# CtDSP_IO.net
KiCad netlist of a schematic drawn in Altium Designer
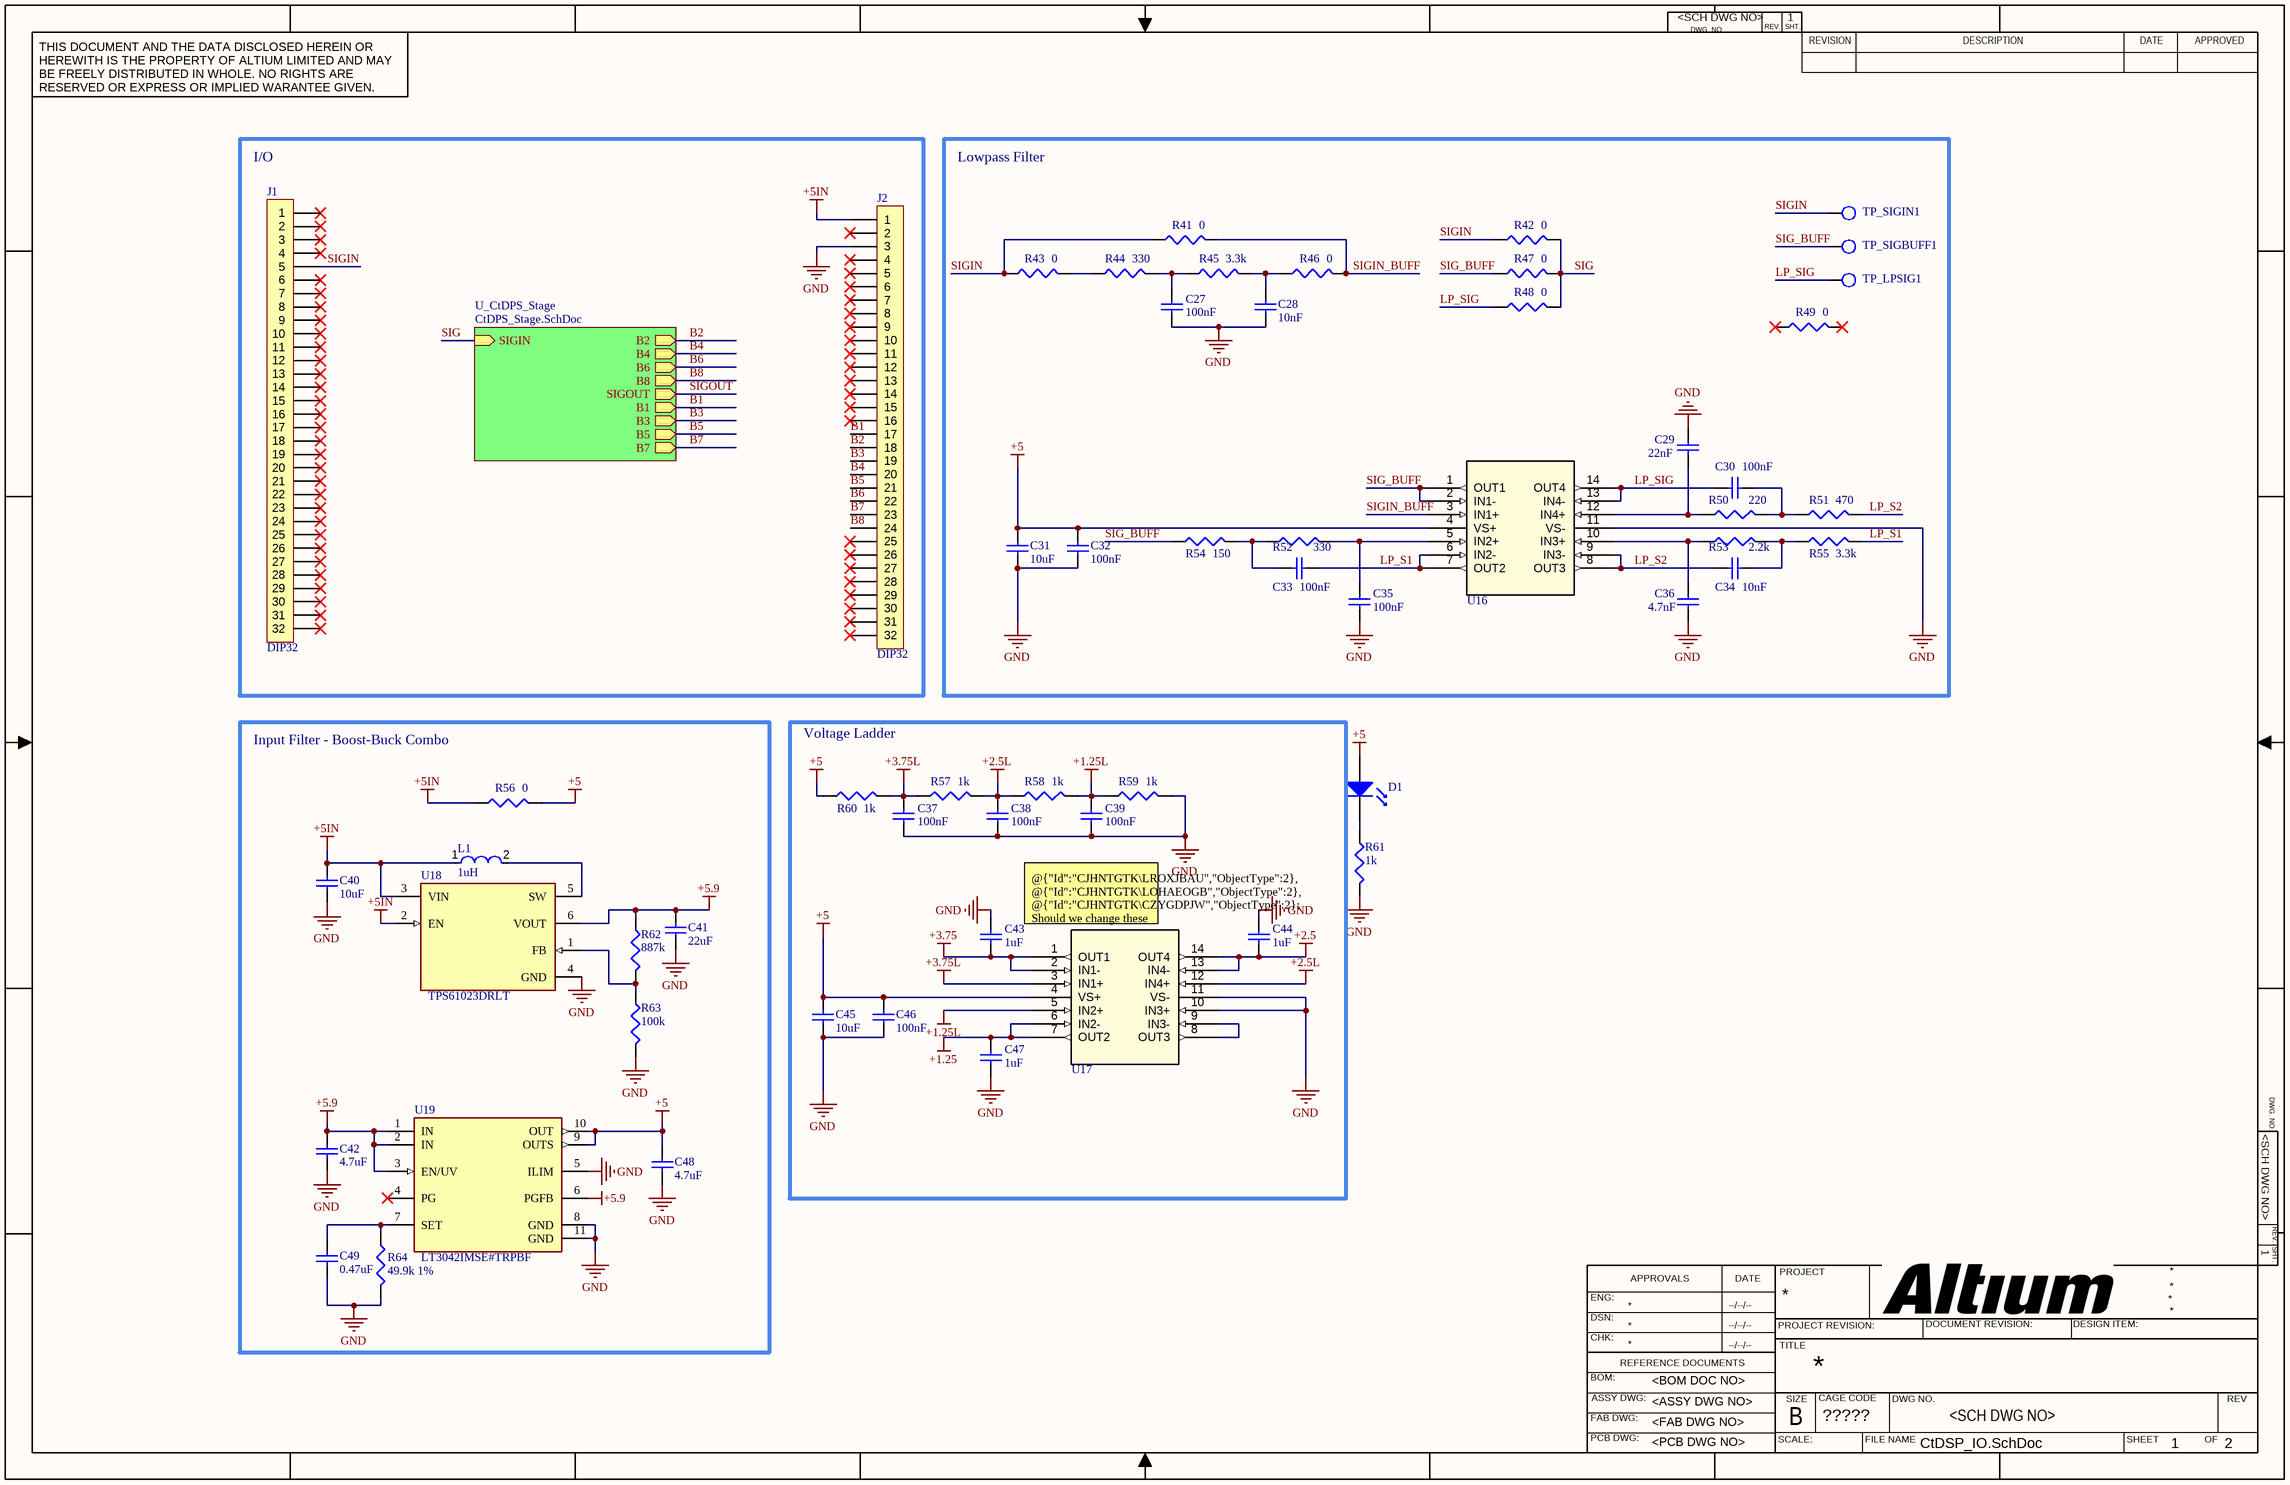
[diagram p0: CtDSP_IO.SchDoc]

(export (version "E")
  (design (tool "Eeschema 10.0.6"))
  (components
    (comp (ref "C27")
      (value "100nF")
      (footprint "C_0402")
      (fields (field (name "LCSC PART #") "C1525"))
      (libsource (lib "ctdsp") (part "C_0402"))
    )
    (comp (ref "C28")
      (value "10nF")
      (footprint "C_0402")
      (fields (field (name "LCSC PART #") "C15195"))
      (libsource (lib "ctdsp") (part "C_0402"))
    )
    (comp (ref "C29")
      (value "22nF")
      (footprint "C_0402")
      (fields (field (name "LCSC PART #") "C1532"))
      (libsource (lib "ctdsp") (part "C_0402"))
    )
    (comp (ref "C30")
      (value "100nF")
      (footprint "C_0402")
      (fields (field (name "LCSC PART #") "C1525"))
      (libsource (lib "ctdsp") (part "C_0402"))
    )
    (comp (ref "C31")
      (value "10uF")
      (footprint "C_0402")
      (fields (field (name "LCSC PART #") "C15525"))
      (libsource (lib "ctdsp") (part "C_0402"))
    )
    (comp (ref "C32")
      (value "100nF")
      (footprint "C_0402")
      (fields (field (name "LCSC PART #") "C1525"))
      (libsource (lib "ctdsp") (part "C_0402"))
    )
    (comp (ref "C33")
      (value "100nF")
      (footprint "C_0402")
      (fields (field (name "LCSC PART #") "C1525"))
      (libsource (lib "ctdsp") (part "C_0402"))
    )
    (comp (ref "C34")
      (value "10nF")
      (footprint "C_0402")
      (fields (field (name "LCSC PART #") "C15195"))
      (libsource (lib "ctdsp") (part "C_0402"))
    )
    (comp (ref "C35")
      (value "100nF")
      (footprint "C_0402")
      (fields (field (name "LCSC PART #") "C1525"))
      (libsource (lib "ctdsp") (part "C_0402"))
    )
    (comp (ref "C36")
      (value "4.7nF")
      (footprint "C_0402")
      (fields (field (name "LCSC PART #") "C1538"))
      (libsource (lib "ctdsp") (part "C_0402"))
    )
    (comp (ref "C37")
      (value "100nF")
      (footprint "C_0402")
      (fields (field (name "LCSC PART #") "C1525"))
      (libsource (lib "ctdsp") (part "C_0402"))
    )
    (comp (ref "C38")
      (value "100nF")
      (footprint "C_0402")
      (fields (field (name "LCSC PART #") "C1525"))
      (libsource (lib "ctdsp") (part "C_0402"))
    )
    (comp (ref "C39")
      (value "100nF")
      (footprint "C_0402")
      (fields (field (name "LCSC PART #") "C1525"))
      (libsource (lib "ctdsp") (part "C_0402"))
    )
    (comp (ref "C40")
      (value "10uF")
      (footprint "C_0402")
      (fields (field (name "LCSC PART #") "C15525"))
      (libsource (lib "ctdsp") (part "C_0402"))
    )
    (comp (ref "C41")
      (value "22uF")
      (footprint "C_0603")
      (fields (field (name "LCSC PART #") "C59461"))
      (libsource (lib "ctdsp") (part "C_0402"))
    )
    (comp (ref "C42")
      (value "4.7uF")
      (footprint "C_0603")
      (fields (field (name "LCSC PART #") "C19666"))
      (libsource (lib "ctdsp") (part "C_0402"))
    )
    (comp (ref "C43")
      (value "1uF")
      (footprint "C_0603")
      (fields (field (name "LCSC PART #") "C15849"))
      (libsource (lib "ctdsp") (part "C_0603"))
    )
    (comp (ref "C44")
      (value "1uF")
      (footprint "C_0603")
      (fields (field (name "LCSC PART #") "C15849"))
      (libsource (lib "ctdsp") (part "C_0603"))
    )
    (comp (ref "C45")
      (value "10uF")
      (footprint "C_0402")
      (fields (field (name "LCSC PART #") "C15525"))
      (libsource (lib "ctdsp") (part "C_0402"))
    )
    (comp (ref "C46")
      (value "100nF")
      (footprint "C_0402")
      (fields (field (name "LCSC PART #") "C1525"))
      (libsource (lib "ctdsp") (part "C_0402"))
    )
    (comp (ref "C47")
      (value "1uF")
      (footprint "C_0603")
      (fields (field (name "LCSC PART #") "C15849"))
      (libsource (lib "ctdsp") (part "C_0603"))
    )
    (comp (ref "C48")
      (value "4.7uF")
      (footprint "C_0603")
      (fields (field (name "LCSC PART #") "C19666"))
      (libsource (lib "ctdsp") (part "C_0402"))
    )
    (comp (ref "C49")
      (value "0.47uF")
      (footprint "C_0603")
      (fields (field (name "LCSC PART #") "C1623"))
      (libsource (lib "ctdsp") (part "C_0402"))
    )
    (comp (ref "D1")
      (value "LED_0603")
      (footprint "LED_6003")
      (fields (field (name "LCSC PART #") "C2286"))
      (libsource (lib "ctdsp") (part "LED_0603"))
    )
    (comp (ref "J1") (value "DIP32") (footprint "DIP32") (libsource (lib "") (part "DIP32_1")))
    (comp (ref "J2") (value "DIP32") (footprint "DIP32") (libsource (lib "ctdsp") (part "DIP32")))
    (comp (ref "L1")
      (value "1uH")
      (footprint "FP-MLP1005D-IPC_C")
      (description "FIXED IND 1UH 500MA 689 MOHM SMD")
      (fields (field (name "TOLERANCE") "20%") (field (name "LCSC PART #") "C531284"))
      (libsource (lib "ctdsp") (part "CMP-08253-000043-1"))
    )
    (comp (ref "R41")
      (value "0")
      (footprint "RES_1206")
      (fields (field (name "LCSC PART #") "C17888"))
      (libsource (lib "ctdsp") (part "RES_1206"))
    )
    (comp (ref "R42")
      (value "0")
      (footprint "RES_1206")
      (fields (field (name "LCSC PART #") "C17888"))
      (libsource (lib "ctdsp") (part "RES_1206"))
    )
    (comp (ref "R43")
      (value "0")
      (footprint "RES_1206")
      (fields (field (name "LCSC PART #") "C17888"))
      (libsource (lib "ctdsp") (part "RES_1206"))
    )
    (comp (ref "R44")
      (value "330")
      (footprint "RES_0603")
      (fields (field (name "LCSC PART #") "C23138"))
      (libsource (lib "ctdsp") (part "RES_0603"))
    )
    (comp (ref "R45")
      (value "3.3k")
      (footprint "RES_0603")
      (fields (field (name "LCSC PART #") "C22978"))
      (libsource (lib "ctdsp") (part "RES_0603"))
    )
    (comp (ref "R46")
      (value "0")
      (footprint "RES_1206")
      (fields (field (name "LCSC PART #") "C17888"))
      (libsource (lib "ctdsp") (part "RES_1206"))
    )
    (comp (ref "R47")
      (value "0")
      (footprint "RES_1206")
      (fields (field (name "LCSC PART #") "C17888"))
      (libsource (lib "ctdsp") (part "RES_1206"))
    )
    (comp (ref "R48")
      (value "0")
      (footprint "RES_1206")
      (fields (field (name "LCSC PART #") "C17888"))
      (libsource (lib "ctdsp") (part "RES_1206"))
    )
    (comp (ref "R49")
      (value "0")
      (footprint "RES_1206")
      (fields (field (name "LCSC PART #") "C17888"))
      (libsource (lib "ctdsp") (part "RES_1206"))
    )
    (comp (ref "R50")
      (value "220")
      (footprint "RES_0402")
      (fields (field (name "LCSC PART #") "C25091"))
      (libsource (lib "ctdsp") (part "RES_0402"))
    )
    (comp (ref "R51")
      (value "470")
      (footprint "RES_0402")
      (fields (field (name "LCSC PART #") "C25117"))
      (libsource (lib "ctdsp") (part "RES_0402"))
    )
    (comp (ref "R52")
      (value "330")
      (footprint "RES_0603")
      (fields (field (name "LCSC PART #") "C23138"))
      (libsource (lib "ctdsp") (part "RES_0603"))
    )
    (comp (ref "R53")
      (value "2.2k")
      (footprint "RES_0603")
      (fields (field (name "LCSC PART #") "C4190"))
      (libsource (lib "ctdsp") (part "RES_0603"))
    )
    (comp (ref "R54")
      (value "150")
      (footprint "RES_0603")
      (fields (field (name "LCSC PART #") "C22808"))
      (libsource (lib "ctdsp") (part "RES_0603"))
    )
    (comp (ref "R55")
      (value "3.3k")
      (footprint "RES_0603")
      (fields (field (name "LCSC PART #") "C22978"))
      (libsource (lib "ctdsp") (part "RES_0603"))
    )
    (comp (ref "R56")
      (value "0")
      (footprint "RES_1206")
      (fields (field (name "LCSC PART #") "C17888"))
      (libsource (lib "ctdsp") (part "RES_1206"))
    )
    (comp (ref "R57")
      (value "1k")
      (footprint "RES_0603")
      (fields (field (name "LCSC PART #") "C5123612"))
      (libsource (lib "ctdsp") (part "RES_0603"))
    )
    (comp (ref "R58")
      (value "1k")
      (footprint "RES_0603")
      (fields (field (name "LCSC PART #") "C5123612"))
      (libsource (lib "ctdsp") (part "RES_0603"))
    )
    (comp (ref "R59")
      (value "1k")
      (footprint "RES_0603")
      (fields (field (name "LCSC PART #") "C5123612"))
      (libsource (lib "ctdsp") (part "RES_0603"))
    )
    (comp (ref "R60")
      (value "1k")
      (footprint "RES_0603")
      (fields (field (name "LCSC PART #") "C5123612"))
      (libsource (lib "ctdsp") (part "RES_0603"))
    )
    (comp (ref "R61")
      (value "1k")
      (footprint "RES_0402")
      (fields (field (name "LCSC PART #") "C11702"))
      (libsource (lib "ctdsp") (part "RES_0402"))
    )
    (comp (ref "R62")
      (value "887k")
      (footprint "RES_0402")
      (fields (field (name "LCSC PART #") "C11547"))
      (libsource (lib "ctdsp") (part "RES_0402"))
    )
    (comp (ref "R63")
      (value "100k")
      (footprint "RES_0402")
      (fields (field (name "LCSC PART #") "C25741"))
      (libsource (lib "ctdsp") (part "RES_0402"))
    )
    (comp (ref "R64")
      (value "49.9k 1%")
      (footprint "RES_0603")
      (fields (field (name "LCSC PART #") "C23184"))
      (libsource (lib "ctdsp") (part "RES_0402"))
    )
    (comp (ref "TP_LPSIG1")
      (value "TESTPOINT")
      (footprint "TESTPOINT")
      (libsource (lib "ctdsp") (part "TESTPOINT"))
    )
    (comp (ref "TP_SIGBUFF1")
      (value "TESTPOINT")
      (footprint "TESTPOINT")
      (libsource (lib "ctdsp") (part "TESTPOINT"))
    )
    (comp (ref "TP_SIGIN1")
      (value "TESTPOINT")
      (footprint "TESTPOINT")
      (libsource (lib "ctdsp") (part "TESTPOINT"))
    )
    (comp (ref "U16")
      (value "ADA4891-4ARZ-R7")
      (footprint "ADA4891-4ARZ-R7")
      (description "Quad Rail-to-Rail Op-Amp, 240 MHz, 170 V/µs, SOT-23-5")
      (fields (field (name "LCSC PART #") "C654290"))
      (libsource (lib "ctdsp") (part "ADA4891-4ARZ-R7"))
    )
    (comp (ref "U17")
      (value "ADA4891-4ARZ-R7")
      (footprint "ADA4891-4ARZ-R7")
      (description "Quad Rail-to-Rail Op-Amp, 240 MHz, 170 V/µs, SOT-23-5")
      (fields (field (name "LCSC PART #") "C654290"))
      (libsource (lib "ctdsp") (part "ADA4891-4ARZ-R7"))
    )
    (comp (ref "U18")
      (value "TPS61023DRLT")
      (footprint "FP-DRL0006A-MFG")
      (description "IC REG BOOST ADJ 3A SOT563")
      (fields (field (name "LCSC PART #") "C1852149"))
      (libsource (lib "ctdsp") (part "CMP-04918-000657-1"))
    )
    (comp (ref "U19")
      (value "LT3042IMSE#TRPBF")
      (footprint "FP-MSE-10-05-08-1664-IPC_A")
      (description "IC REG LIN POS ADJ 200MA 10MSOP")
      (fields (field (name "LCSC PART #") "C666569"))
      (libsource (lib "ctdsp") (part "CMP-09138-000225-1"))
    )
  )
  (nets
    (net (code "1") (name "+1.25") (class "Default")
      (node (ref "C47") (pin "2") (pinfunction "2_2") (pintype "passive"))
      (node (ref "U17") (pin "6") (pinfunction "IN2-_6") (pintype "input"))
      (node (ref "U17") (pin "7") (pinfunction "OUT2_7") (pintype "output"))
    )
    (net (code "2") (name "+1.25L") (class "Default")
      (node (ref "C39") (pin "2") (pinfunction "2_2") (pintype "passive"))
      (node (ref "R58") (pin "2") (pinfunction "2_2") (pintype "passive"))
      (node (ref "R59") (pin "1") (pinfunction "1_1") (pintype "passive"))
      (node (ref "U17") (pin "5") (pinfunction "IN2+_5") (pintype "input"))
    )
    (net (code "3") (name "+2.5") (class "Default")
      (node (ref "C44") (pin "1") (pinfunction "1_1") (pintype "passive"))
      (node (ref "U17") (pin "13") (pinfunction "IN4-_13") (pintype "input"))
      (node (ref "U17") (pin "14") (pinfunction "OUT4_14") (pintype "output"))
    )
    (net (code "4") (name "+2.5L") (class "Default")
      (node (ref "C38") (pin "2") (pinfunction "2_2") (pintype "passive"))
      (node (ref "R57") (pin "2") (pinfunction "2_2") (pintype "passive"))
      (node (ref "R58") (pin "1") (pinfunction "1_1") (pintype "passive"))
      (node (ref "U17") (pin "12") (pinfunction "IN4+_12") (pintype "input"))
    )
    (net (code "5") (name "+3.75") (class "Default")
      (node (ref "C43") (pin "1") (pinfunction "1_1") (pintype "passive"))
      (node (ref "U17") (pin "1") (pinfunction "OUT1_1") (pintype "output"))
      (node (ref "U17") (pin "2") (pinfunction "IN1-_2") (pintype "input"))
    )
    (net (code "6") (name "+3.75L") (class "Default")
      (node (ref "C37") (pin "2") (pinfunction "2_2") (pintype "passive"))
      (node (ref "R57") (pin "1") (pinfunction "1_1") (pintype "passive"))
      (node (ref "R60") (pin "2") (pinfunction "2_2") (pintype "passive"))
      (node (ref "U17") (pin "3") (pinfunction "IN1+_3") (pintype "input"))
    )
    (net (code "7") (name "+5") (class "Default")
      (node (ref "C31") (pin "1") (pinfunction "1_1") (pintype "passive"))
      (node (ref "C32") (pin "2") (pinfunction "2_2") (pintype "passive"))
      (node (ref "C45") (pin "1") (pinfunction "1_1") (pintype "passive"))
      (node (ref "C46") (pin "2") (pinfunction "2_2") (pintype "passive"))
      (node (ref "C48") (pin "2") (pinfunction "2_2") (pintype "passive"))
      (node (ref "D1") (pin "2") (pinfunction "K_2") (pintype "passive"))
      (node (ref "R56") (pin "2") (pinfunction "2_2") (pintype "passive"))
      (node (ref "R60") (pin "1") (pinfunction "1_1") (pintype "passive"))
      (node (ref "U16") (pin "4") (pinfunction "VS+_4") (pintype "power_in"))
      (node (ref "U17") (pin "4") (pinfunction "VS+_4") (pintype "power_in"))
      (node (ref "U19") (pin "10") (pinfunction "OUT_10") (pintype "output"))
      (node (ref "U19") (pin "9") (pinfunction "OUTS_9") (pintype "output"))
    )
    (net (code "8") (name "+5.9") (class "Default")
      (node (ref "C41") (pin "2") (pinfunction "2_2") (pintype "passive"))
      (node (ref "C42") (pin "2") (pinfunction "2_2") (pintype "passive"))
      (node (ref "R62") (pin "1") (pinfunction "1_1") (pintype "passive"))
      (node (ref "U18") (pin "6") (pinfunction "VOUT_6") (pintype "power_in"))
      (node (ref "U19") (pin "1") (pinfunction "IN_1") (pintype "power_in"))
      (node (ref "U19") (pin "2") (pinfunction "IN_2") (pintype "power_in"))
      (node (ref "U19") (pin "3") (pinfunction "EN/UV_3") (pintype "input"))
      (node (ref "U19") (pin "6") (pinfunction "PGFB_6") (pintype "passive"))
    )
    (net (code "9") (name "+5IN") (class "Default")
      (node (ref "C40") (pin "2") (pinfunction "2_2") (pintype "passive"))
      (node (ref "J2") (pin "1") (pinfunction "1_1") (pintype "passive"))
      (node (ref "L1") (pin "1") (pinfunction "1_1") (pintype "passive"))
      (node (ref "R56") (pin "1") (pinfunction "1_1") (pintype "passive"))
      (node (ref "U18") (pin "2") (pinfunction "EN_2") (pintype "input"))
      (node (ref "U18") (pin "3") (pinfunction "VIN_3") (pintype "power_in"))
    )
    (net (code "10") (name "/B1") (class "Default")
      (node (ref "J2") (pin "17") (pinfunction "17_17") (pintype "passive"))
    )
    (net (code "11") (name "/B2") (class "Default")
      (node (ref "J2") (pin "18") (pinfunction "18_18") (pintype "passive"))
    )
    (net (code "12") (name "/B3") (class "Default")
      (node (ref "J2") (pin "19") (pinfunction "19_19") (pintype "passive"))
    )
    (net (code "13") (name "/B4") (class "Default")
      (node (ref "J2") (pin "20") (pinfunction "20_20") (pintype "passive"))
    )
    (net (code "14") (name "/B5") (class "Default")
      (node (ref "J2") (pin "21") (pinfunction "21_21") (pintype "passive"))
    )
    (net (code "15") (name "/B6") (class "Default")
      (node (ref "J2") (pin "22") (pinfunction "22_22") (pintype "passive"))
    )
    (net (code "16") (name "/B7") (class "Default")
      (node (ref "J2") (pin "23") (pinfunction "23_23") (pintype "passive"))
    )
    (net (code "17") (name "/B8") (class "Default")
      (node (ref "J2") (pin "24") (pinfunction "24_24") (pintype "passive"))
    )
    (net (code "18") (name "/LP_S1") (class "Default")
      (node (ref "C33") (pin "1") (pinfunction "1_1") (pintype "passive"))
      (node (ref "R55") (pin "2") (pinfunction "2_2") (pintype "passive"))
      (node (ref "U16") (pin "6") (pinfunction "IN2-_6") (pintype "input"))
      (node (ref "U16") (pin "7") (pinfunction "OUT2_7") (pintype "output"))
    )
    (net (code "19") (name "/LP_S2") (class "Default")
      (node (ref "C34") (pin "1") (pinfunction "1_1") (pintype "passive"))
      (node (ref "R51") (pin "2") (pinfunction "2_2") (pintype "passive"))
      (node (ref "U16") (pin "8") (pinfunction "OUT3_8") (pintype "output"))
      (node (ref "U16") (pin "9") (pinfunction "IN3-_9") (pintype "input"))
    )
    (net (code "20") (name "/LP_SIG") (class "Default")
      (node (ref "C30") (pin "2") (pinfunction "2_2") (pintype "passive"))
      (node (ref "R48") (pin "1") (pinfunction "1_1") (pintype "passive"))
      (node (ref "TP_LPSIG1") (pin "1") (pinfunction "1_1") (pintype "passive"))
      (node (ref "U16") (pin "13") (pinfunction "IN4-_13") (pintype "input"))
      (node (ref "U16") (pin "14") (pinfunction "OUT4_14") (pintype "output"))
    )
    (net (code "21") (name "/SIG") (class "Default")
      (node (ref "R42") (pin "2") (pinfunction "2_2") (pintype "passive"))
      (node (ref "R47") (pin "2") (pinfunction "2_2") (pintype "passive"))
      (node (ref "R48") (pin "2") (pinfunction "2_2") (pintype "passive"))
    )
    (net (code "22") (name "/SIGIN") (class "Default")
      (node (ref "J1") (pin "5") (pinfunction "5_5") (pintype "passive"))
      (node (ref "R41") (pin "1") (pinfunction "1_1") (pintype "passive"))
      (node (ref "R42") (pin "1") (pinfunction "1_1") (pintype "passive"))
      (node (ref "R43") (pin "1") (pinfunction "1_1") (pintype "passive"))
      (node (ref "TP_SIGIN1") (pin "1") (pinfunction "1_1") (pintype "passive"))
    )
    (net (code "23") (name "/SIGIN_BUFF") (class "Default")
      (node (ref "R41") (pin "2") (pinfunction "2_2") (pintype "passive"))
      (node (ref "R46") (pin "2") (pinfunction "2_2") (pintype "passive"))
      (node (ref "U16") (pin "3") (pinfunction "IN1+_3") (pintype "input"))
    )
    (net (code "25") (name "/SIG_BUFF") (class "Default")
      (node (ref "R47") (pin "1") (pinfunction "1_1") (pintype "passive"))
      (node (ref "R54") (pin "1") (pinfunction "1_1") (pintype "passive"))
      (node (ref "TP_SIGBUFF1") (pin "1") (pinfunction "1_1") (pintype "passive"))
      (node (ref "U16") (pin "1") (pinfunction "OUT1_1") (pintype "output"))
      (node (ref "U16") (pin "2") (pinfunction "IN1-_2") (pintype "input"))
    )
    (net (code "26") (name "GND") (class "Default")
      (node (ref "C27") (pin "1") (pinfunction "1_1") (pintype "passive"))
      (node (ref "C28") (pin "1") (pinfunction "1_1") (pintype "passive"))
      (node (ref "C29") (pin "2") (pinfunction "2_2") (pintype "passive"))
      (node (ref "C31") (pin "2") (pinfunction "2_2") (pintype "passive"))
      (node (ref "C32") (pin "1") (pinfunction "1_1") (pintype "passive"))
      (node (ref "C35") (pin "1") (pinfunction "1_1") (pintype "passive"))
      (node (ref "C36") (pin "1") (pinfunction "1_1") (pintype "passive"))
      (node (ref "C37") (pin "1") (pinfunction "1_1") (pintype "passive"))
      (node (ref "C38") (pin "1") (pinfunction "1_1") (pintype "passive"))
      (node (ref "C39") (pin "1") (pinfunction "1_1") (pintype "passive"))
      (node (ref "C40") (pin "1") (pinfunction "1_1") (pintype "passive"))
      (node (ref "C41") (pin "1") (pinfunction "1_1") (pintype "passive"))
      (node (ref "C42") (pin "1") (pinfunction "1_1") (pintype "passive"))
      (node (ref "C43") (pin "2") (pinfunction "2_2") (pintype "passive"))
      (node (ref "C44") (pin "2") (pinfunction "2_2") (pintype "passive"))
      (node (ref "C45") (pin "2") (pinfunction "2_2") (pintype "passive"))
      (node (ref "C46") (pin "1") (pinfunction "1_1") (pintype "passive"))
      (node (ref "C47") (pin "1") (pinfunction "1_1") (pintype "passive"))
      (node (ref "C48") (pin "1") (pinfunction "1_1") (pintype "passive"))
      (node (ref "C49") (pin "1") (pinfunction "1_1") (pintype "passive"))
      (node (ref "J2") (pin "3") (pinfunction "3_3") (pintype "passive"))
      (node (ref "R59") (pin "2") (pinfunction "2_2") (pintype "passive"))
      (node (ref "R61") (pin "2") (pinfunction "2_2") (pintype "passive"))
      (node (ref "R63") (pin "2") (pinfunction "2_2") (pintype "passive"))
      (node (ref "R64") (pin "2") (pinfunction "2_2") (pintype "passive"))
      (node (ref "U16") (pin "11") (pinfunction "VS-_11") (pintype "power_in"))
      (node (ref "U17") (pin "10") (pinfunction "IN3+_10") (pintype "input"))
      (node (ref "U17") (pin "11") (pinfunction "VS-_11") (pintype "power_in"))
      (node (ref "U18") (pin "4") (pinfunction "GND_4") (pintype "power_in"))
      (node (ref "U19") (pin "11") (pinfunction "GND_11") (pintype "power_in"))
      (node (ref "U19") (pin "5") (pinfunction "ILIM_5") (pintype "passive"))
      (node (ref "U19") (pin "8") (pinfunction "GND_8") (pintype "power_in"))
    )
    (net (code "27") (name "Net-(C27-Pad2)") (class "Default")
      (node (ref "C27") (pin "2") (pinfunction "2_2") (pintype "passive"))
      (node (ref "R44") (pin "2") (pinfunction "2_2") (pintype "passive"))
      (node (ref "R45") (pin "1") (pinfunction "1_1") (pintype "passive"))
    )
    (net (code "28") (name "Net-(C28-Pad2)") (class "Default")
      (node (ref "C28") (pin "2") (pinfunction "2_2") (pintype "passive"))
      (node (ref "R45") (pin "2") (pinfunction "2_2") (pintype "passive"))
      (node (ref "R46") (pin "1") (pinfunction "1_1") (pintype "passive"))
    )
    (net (code "29") (name "Net-(C30-Pad1)") (class "Default")
      (node (ref "C30") (pin "1") (pinfunction "1_1") (pintype "passive"))
      (node (ref "R50") (pin "2") (pinfunction "2_2") (pintype "passive"))
      (node (ref "R51") (pin "1") (pinfunction "1_1") (pintype "passive"))
    )
    (net (code "30") (name "Net-(C33-Pad2)") (class "Default")
      (node (ref "C33") (pin "2") (pinfunction "2_2") (pintype "passive"))
      (node (ref "R52") (pin "1") (pinfunction "1_1") (pintype "passive"))
      (node (ref "R54") (pin "2") (pinfunction "2_2") (pintype "passive"))
    )
    (net (code "31") (name "Net-(C34-Pad2)") (class "Default")
      (node (ref "C34") (pin "2") (pinfunction "2_2") (pintype "passive"))
      (node (ref "R53") (pin "2") (pinfunction "2_2") (pintype "passive"))
      (node (ref "R55") (pin "1") (pinfunction "1_1") (pintype "passive"))
    )
    (net (code "32") (name "Net-(D1-A)") (class "Default")
      (node (ref "D1") (pin "1") (pinfunction "A_1") (pintype "passive"))
      (node (ref "R61") (pin "1") (pinfunction "1_1") (pintype "passive"))
    )
    (net (code "33") (name "Net-(R43-Pad2)") (class "Default")
      (node (ref "R43") (pin "2") (pinfunction "2_2") (pintype "passive"))
      (node (ref "R44") (pin "1") (pinfunction "1_1") (pintype "passive"))
    )
    (net (code "34") (name "Net-(U16-IN2+)") (class "Default")
      (node (ref "C35") (pin "2") (pinfunction "2_2") (pintype "passive"))
      (node (ref "R52") (pin "2") (pinfunction "2_2") (pintype "passive"))
      (node (ref "U16") (pin "5") (pinfunction "IN2+_5") (pintype "input"))
    )
    (net (code "35") (name "Net-(U16-IN3+)") (class "Default")
      (node (ref "C36") (pin "2") (pinfunction "2_2") (pintype "passive"))
      (node (ref "R53") (pin "1") (pinfunction "1_1") (pintype "passive"))
      (node (ref "U16") (pin "10") (pinfunction "IN3+_10") (pintype "input"))
    )
    (net (code "36") (name "Net-(U16-IN4+)") (class "Default")
      (node (ref "C29") (pin "1") (pinfunction "1_1") (pintype "passive"))
      (node (ref "R50") (pin "1") (pinfunction "1_1") (pintype "passive"))
      (node (ref "U16") (pin "12") (pinfunction "IN4+_12") (pintype "input"))
    )
    (net (code "37") (name "Net-(U17-IN3-)") (class "Default")
      (node (ref "U17") (pin "8") (pinfunction "OUT3_8") (pintype "output"))
      (node (ref "U17") (pin "9") (pinfunction "IN3-_9") (pintype "input"))
    )
    (net (code "38") (name "Net-(U18-FB)") (class "Default")
      (node (ref "R62") (pin "2") (pinfunction "2_2") (pintype "passive"))
      (node (ref "R63") (pin "1") (pinfunction "1_1") (pintype "passive"))
      (node (ref "U18") (pin "1") (pinfunction "FB_1") (pintype "input"))
    )
    (net (code "39") (name "Net-(U18-SW)") (class "Default")
      (node (ref "L1") (pin "2") (pinfunction "2_2") (pintype "passive"))
      (node (ref "U18") (pin "5") (pinfunction "SW_5") (pintype "passive"))
    )
    (net (code "40") (name "Net-(U19-SET)") (class "Default")
      (node (ref "C49") (pin "2") (pinfunction "2_2") (pintype "passive"))
      (node (ref "R64") (pin "1") (pinfunction "1_1") (pintype "passive"))
      (node (ref "U19") (pin "7") (pinfunction "SET_7") (pintype "passive"))
    )
    (net (code "41") (name "unconnected-(J1-Pad1)") (class "Default")
      (node (ref "J1") (pin "1") (pinfunction "1_1") (pintype "passive+no_connect"))
    )
    (net (code "42") (name "unconnected-(J1-Pad2)") (class "Default")
      (node (ref "J1") (pin "2") (pinfunction "2_2") (pintype "passive+no_connect"))
    )
    (net (code "43") (name "unconnected-(J1-Pad3)") (class "Default")
      (node (ref "J1") (pin "3") (pinfunction "3_3") (pintype "passive+no_connect"))
    )
    (net (code "44") (name "unconnected-(J1-Pad4)") (class "Default")
      (node (ref "J1") (pin "4") (pinfunction "4_4") (pintype "passive+no_connect"))
    )
    (net (code "45") (name "unconnected-(J1-Pad6)") (class "Default")
      (node (ref "J1") (pin "6") (pinfunction "6_6") (pintype "passive+no_connect"))
    )
    (net (code "46") (name "unconnected-(J1-Pad7)") (class "Default")
      (node (ref "J1") (pin "7") (pinfunction "7_7") (pintype "passive+no_connect"))
    )
    (net (code "47") (name "unconnected-(J1-Pad8)") (class "Default")
      (node (ref "J1") (pin "8") (pinfunction "8_8") (pintype "passive+no_connect"))
    )
    (net (code "48") (name "unconnected-(J1-Pad9)") (class "Default")
      (node (ref "J1") (pin "9") (pinfunction "9_9") (pintype "passive+no_connect"))
    )
    (net (code "49") (name "unconnected-(J1-Pad10)") (class "Default")
      (node (ref "J1") (pin "10") (pinfunction "10_10") (pintype "passive+no_connect"))
    )
    (net (code "50") (name "unconnected-(J1-Pad11)") (class "Default")
      (node (ref "J1") (pin "11") (pinfunction "11_11") (pintype "passive+no_connect"))
    )
    (net (code "51") (name "unconnected-(J1-Pad12)") (class "Default")
      (node (ref "J1") (pin "12") (pinfunction "12_12") (pintype "passive+no_connect"))
    )
    (net (code "52") (name "unconnected-(J1-Pad13)") (class "Default")
      (node (ref "J1") (pin "13") (pinfunction "13_13") (pintype "passive+no_connect"))
    )
    (net (code "53") (name "unconnected-(J1-Pad14)") (class "Default")
      (node (ref "J1") (pin "14") (pinfunction "14_14") (pintype "passive+no_connect"))
    )
    (net (code "54") (name "unconnected-(J1-Pad15)") (class "Default")
      (node (ref "J1") (pin "15") (pinfunction "15_15") (pintype "passive+no_connect"))
    )
    (net (code "55") (name "unconnected-(J1-Pad16)") (class "Default")
      (node (ref "J1") (pin "16") (pinfunction "16_16") (pintype "passive+no_connect"))
    )
    (net (code "56") (name "unconnected-(J1-Pad17)") (class "Default")
      (node (ref "J1") (pin "17") (pinfunction "17_17") (pintype "passive+no_connect"))
    )
    (net (code "57") (name "unconnected-(J1-Pad18)") (class "Default")
      (node (ref "J1") (pin "18") (pinfunction "18_18") (pintype "passive+no_connect"))
    )
    (net (code "58") (name "unconnected-(J1-Pad19)") (class "Default")
      (node (ref "J1") (pin "19") (pinfunction "19_19") (pintype "passive+no_connect"))
    )
    (net (code "59") (name "unconnected-(J1-Pad20)") (class "Default")
      (node (ref "J1") (pin "20") (pinfunction "20_20") (pintype "passive+no_connect"))
    )
    (net (code "60") (name "unconnected-(J1-Pad21)") (class "Default")
      (node (ref "J1") (pin "21") (pinfunction "21_21") (pintype "passive+no_connect"))
    )
    (net (code "61") (name "unconnected-(J1-Pad22)") (class "Default")
      (node (ref "J1") (pin "22") (pinfunction "22_22") (pintype "passive+no_connect"))
    )
    (net (code "62") (name "unconnected-(J1-Pad23)") (class "Default")
      (node (ref "J1") (pin "23") (pinfunction "23_23") (pintype "passive+no_connect"))
    )
    (net (code "63") (name "unconnected-(J1-Pad24)") (class "Default")
      (node (ref "J1") (pin "24") (pinfunction "24_24") (pintype "passive+no_connect"))
    )
    (net (code "64") (name "unconnected-(J1-Pad25)") (class "Default")
      (node (ref "J1") (pin "25") (pinfunction "25_25") (pintype "passive+no_connect"))
    )
    (net (code "65") (name "unconnected-(J1-Pad26)") (class "Default")
      (node (ref "J1") (pin "26") (pinfunction "26_26") (pintype "passive+no_connect"))
    )
    (net (code "66") (name "unconnected-(J1-Pad27)") (class "Default")
      (node (ref "J1") (pin "27") (pinfunction "27_27") (pintype "passive+no_connect"))
    )
    (net (code "67") (name "unconnected-(J1-Pad28)") (class "Default")
      (node (ref "J1") (pin "28") (pinfunction "28_28") (pintype "passive+no_connect"))
    )
    (net (code "68") (name "unconnected-(J1-Pad29)") (class "Default")
      (node (ref "J1") (pin "29") (pinfunction "29_29") (pintype "passive+no_connect"))
    )
    (net (code "69") (name "unconnected-(J1-Pad30)") (class "Default")
      (node (ref "J1") (pin "30") (pinfunction "30_30") (pintype "passive+no_connect"))
    )
    (net (code "70") (name "unconnected-(J1-Pad31)") (class "Default")
      (node (ref "J1") (pin "31") (pinfunction "31_31") (pintype "passive+no_connect"))
    )
    (net (code "71") (name "unconnected-(J1-Pad32)") (class "Default")
      (node (ref "J1") (pin "32") (pinfunction "32_32") (pintype "passive+no_connect"))
    )
    (net (code "72") (name "unconnected-(J2-Pad2)") (class "Default")
      (node (ref "J2") (pin "2") (pinfunction "2_2") (pintype "passive+no_connect"))
    )
    (net (code "73") (name "unconnected-(J2-Pad4)") (class "Default")
      (node (ref "J2") (pin "4") (pinfunction "4_4") (pintype "passive+no_connect"))
    )
    (net (code "74") (name "unconnected-(J2-Pad5)") (class "Default")
      (node (ref "J2") (pin "5") (pinfunction "5_5") (pintype "passive+no_connect"))
    )
    (net (code "75") (name "unconnected-(J2-Pad6)") (class "Default")
      (node (ref "J2") (pin "6") (pinfunction "6_6") (pintype "passive+no_connect"))
    )
    (net (code "76") (name "unconnected-(J2-Pad7)") (class "Default")
      (node (ref "J2") (pin "7") (pinfunction "7_7") (pintype "passive+no_connect"))
    )
    (net (code "77") (name "unconnected-(J2-Pad8)") (class "Default")
      (node (ref "J2") (pin "8") (pinfunction "8_8") (pintype "passive+no_connect"))
    )
    (net (code "78") (name "unconnected-(J2-Pad9)") (class "Default")
      (node (ref "J2") (pin "9") (pinfunction "9_9") (pintype "passive+no_connect"))
    )
    (net (code "79") (name "unconnected-(J2-Pad10)") (class "Default")
      (node (ref "J2") (pin "10") (pinfunction "10_10") (pintype "passive+no_connect"))
    )
    (net (code "80") (name "unconnected-(J2-Pad11)") (class "Default")
      (node (ref "J2") (pin "11") (pinfunction "11_11") (pintype "passive+no_connect"))
    )
    (net (code "81") (name "unconnected-(J2-Pad12)") (class "Default")
      (node (ref "J2") (pin "12") (pinfunction "12_12") (pintype "passive+no_connect"))
    )
    (net (code "82") (name "unconnected-(J2-Pad13)") (class "Default")
      (node (ref "J2") (pin "13") (pinfunction "13_13") (pintype "passive+no_connect"))
    )
    (net (code "83") (name "unconnected-(J2-Pad14)") (class "Default")
      (node (ref "J2") (pin "14") (pinfunction "14_14") (pintype "passive+no_connect"))
    )
    (net (code "84") (name "unconnected-(J2-Pad15)") (class "Default")
      (node (ref "J2") (pin "15") (pinfunction "15_15") (pintype "passive+no_connect"))
    )
    (net (code "85") (name "unconnected-(J2-Pad16)") (class "Default")
      (node (ref "J2") (pin "16") (pinfunction "16_16") (pintype "passive+no_connect"))
    )
    (net (code "86") (name "unconnected-(J2-Pad25)") (class "Default")
      (node (ref "J2") (pin "25") (pinfunction "25_25") (pintype "passive+no_connect"))
    )
    (net (code "87") (name "unconnected-(J2-Pad26)") (class "Default")
      (node (ref "J2") (pin "26") (pinfunction "26_26") (pintype "passive+no_connect"))
    )
    (net (code "88") (name "unconnected-(J2-Pad27)") (class "Default")
      (node (ref "J2") (pin "27") (pinfunction "27_27") (pintype "passive+no_connect"))
    )
    (net (code "89") (name "unconnected-(J2-Pad28)") (class "Default")
      (node (ref "J2") (pin "28") (pinfunction "28_28") (pintype "passive+no_connect"))
    )
    (net (code "90") (name "unconnected-(J2-Pad29)") (class "Default")
      (node (ref "J2") (pin "29") (pinfunction "29_29") (pintype "passive+no_connect"))
    )
    (net (code "91") (name "unconnected-(J2-Pad30)") (class "Default")
      (node (ref "J2") (pin "30") (pinfunction "30_30") (pintype "passive+no_connect"))
    )
    (net (code "92") (name "unconnected-(J2-Pad31)") (class "Default")
      (node (ref "J2") (pin "31") (pinfunction "31_31") (pintype "passive+no_connect"))
    )
    (net (code "93") (name "unconnected-(J2-Pad32)") (class "Default")
      (node (ref "J2") (pin "32") (pinfunction "32_32") (pintype "passive+no_connect"))
    )
    (net (code "94") (name "unconnected-(R49-Pad1)") (class "Default")
      (node (ref "R49") (pin "1") (pinfunction "1_1") (pintype "passive+no_connect"))
    )
    (net (code "95") (name "unconnected-(R49-Pad2)") (class "Default")
      (node (ref "R49") (pin "2") (pinfunction "2_2") (pintype "passive+no_connect"))
    )
    (net (code "96") (name "unconnected-(U19-PG-Pad4)") (class "Default")
      (node (ref "U19") (pin "4") (pinfunction "PG_4") (pintype "open_collector+no_connect"))
    )
  )
)
